# Sheet3.net
KiCad netlist of a schematic drawn in Altium Designer
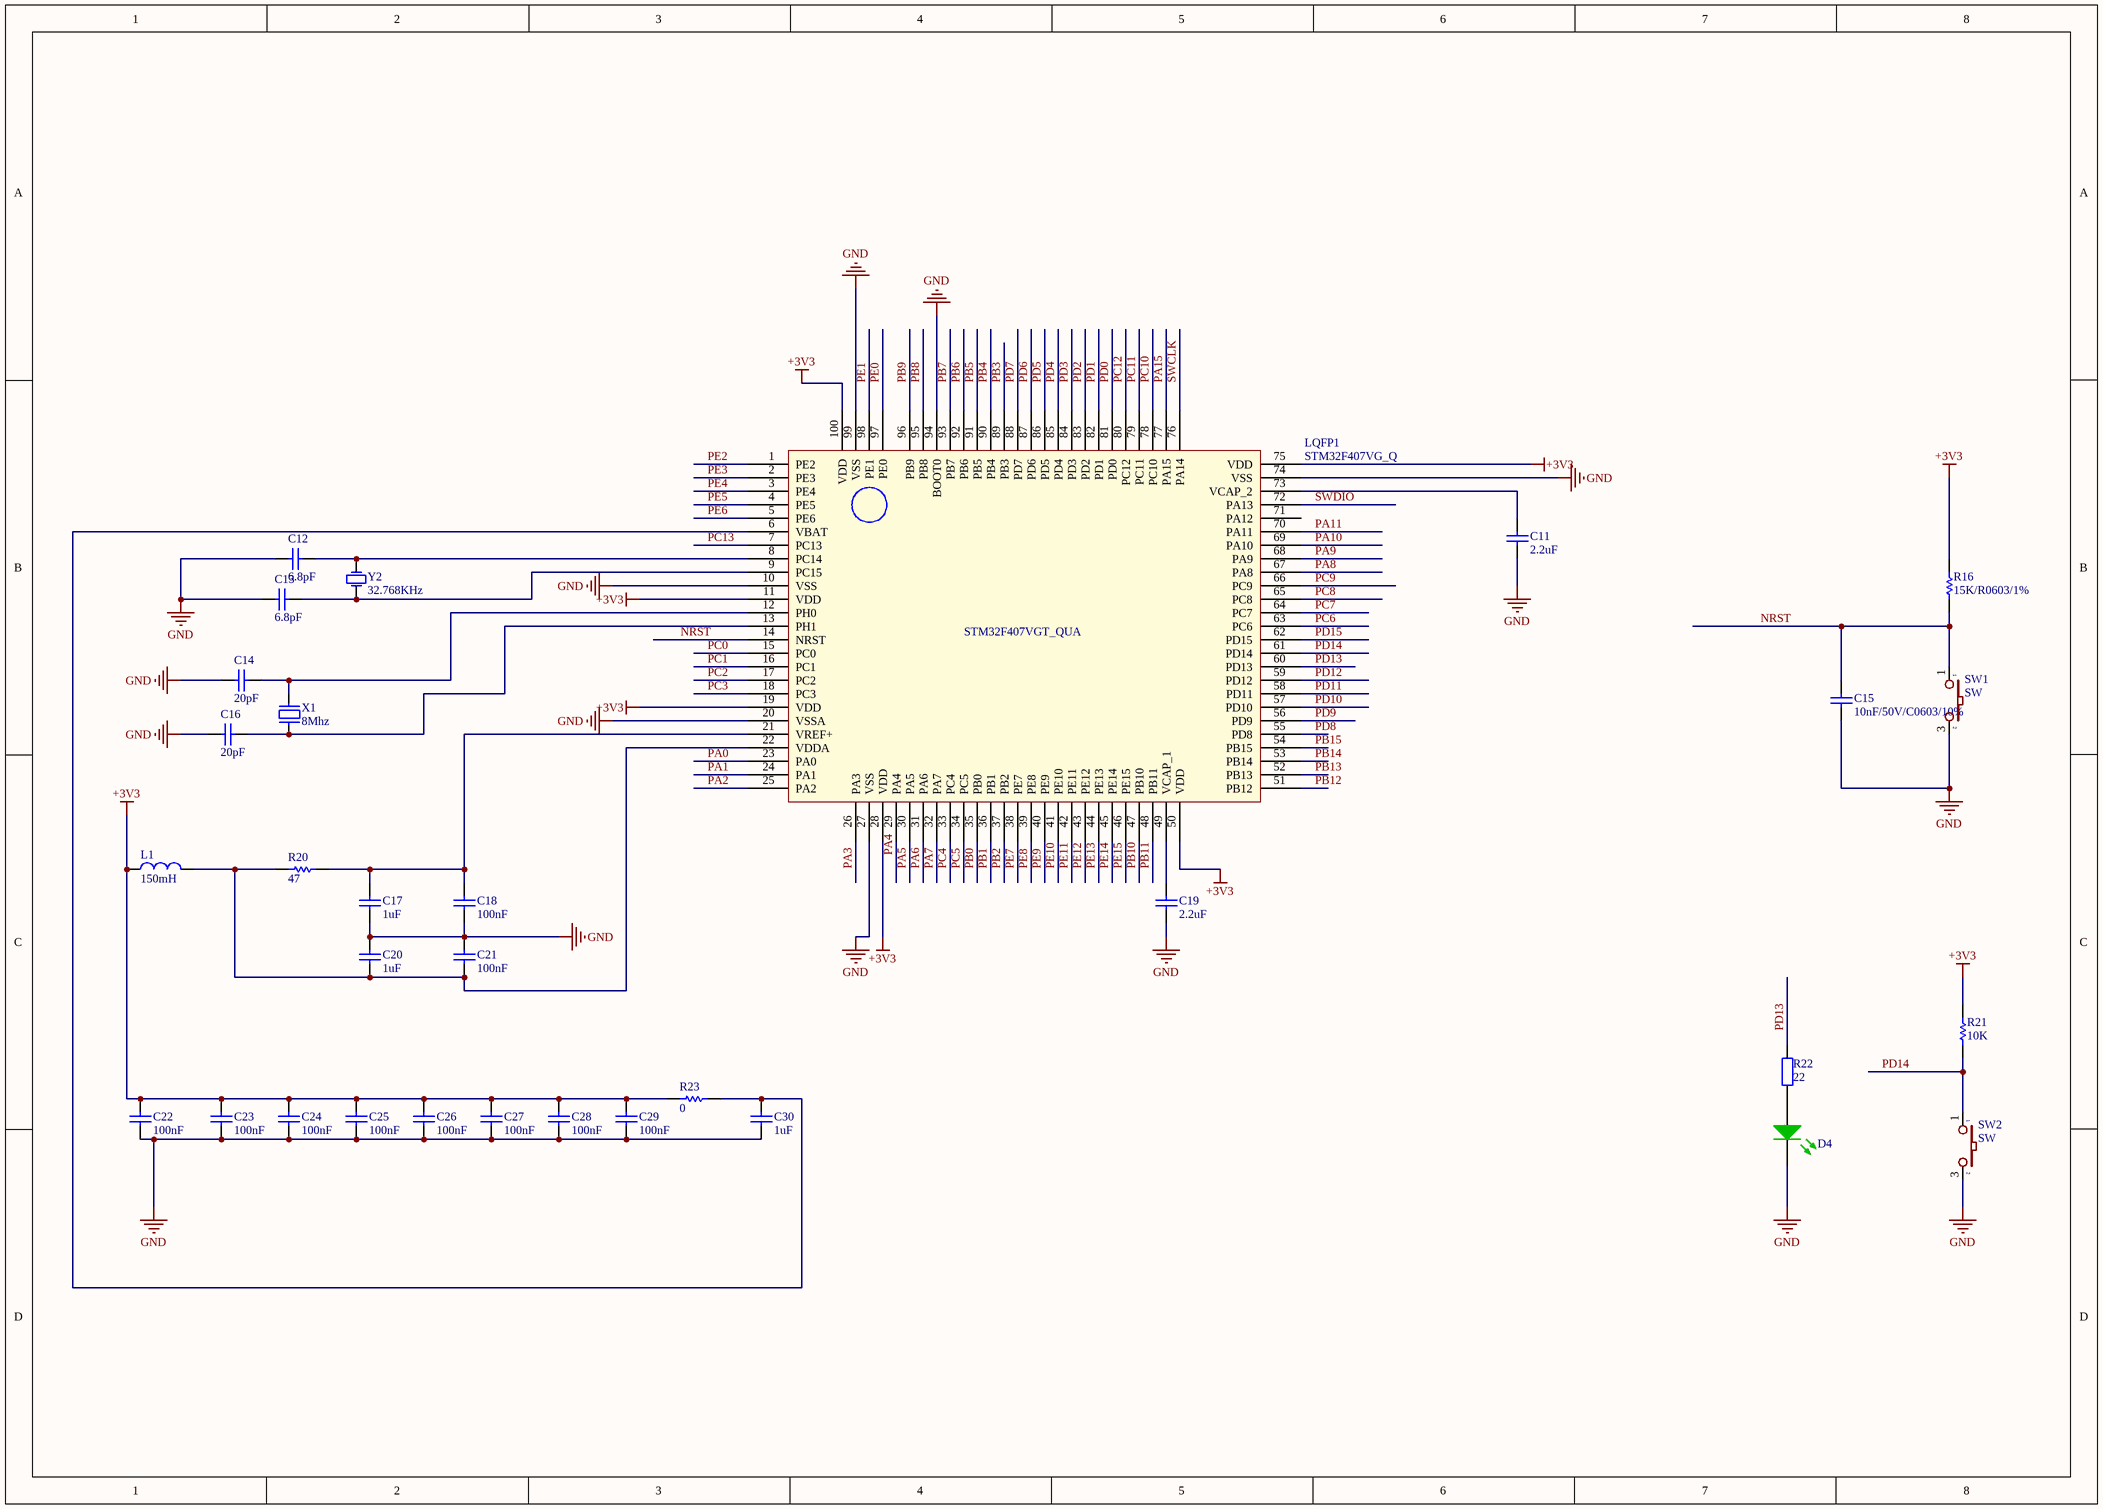
[diagram p0: Sheet3.SchDoc]

(export (version "E")
  (design (tool "Eeschema 10.0.6"))
  (components
    (comp (ref "C11")
      (value "2.2uF")
      (footprint "Cap Ceramic 0805 SMD")
      (description "CAP CER 22PF 50V NP0 0603")
      (fields
        (field (name "MANUFACTURER") "Kemet")
        (field (name "MANUFACTURER PART NUMBER") "C0603C220K5GACTU")
      )
      (libsource (lib "lpson") (part "22pF/50V/C0603/10%"))
    )
    (comp (ref "C12")
      (value "6.8pF")
      (footprint "Cap Ceramic 0805 SMD")
      (description "CAP CER 22PF 50V NP0 0603")
      (fields
        (field (name "MANUFACTURER") "Kemet")
        (field (name "MANUFACTURER PART NUMBER") "C0603C220K5GACTU")
      )
      (libsource (lib "lpson") (part "22pF/50V/C0603/10%"))
    )
    (comp (ref "C13")
      (value "6.8pF")
      (footprint "Cap Ceramic 0805 SMD")
      (description "CAP CER 22PF 50V NP0 0603")
      (fields
        (field (name "MANUFACTURER") "Kemet")
        (field (name "MANUFACTURER PART NUMBER") "C0603C220K5GACTU")
      )
      (libsource (lib "lpson") (part "22pF/50V/C0603/10%"))
    )
    (comp (ref "C14")
      (value "20pF")
      (footprint "Cap Ceramic 0805 SMD")
      (description "CAP CER 22PF 50V NP0 0603")
      (fields
        (field (name "MANUFACTURER") "Kemet")
        (field (name "MANUFACTURER PART NUMBER") "C0603C220K5GACTU")
      )
      (libsource (lib "lpson") (part "22pF/50V/C0603/10%"))
    )
    (comp (ref "C15")
      (value "10nF/50V/C0603/10%")
      (footprint "Cap Ceramic 0805 SMD")
      (description "CAP CER 10000PF 50V X7R 0603")
      (fields
        (field (name "MANUFACTURER") "Murata Electronics North America")
        (field (name "MANUFACTURER PART NUMBER") "GRM188R71H103KA01D")
      )
      (libsource (lib "lpson") (part "10nF/50V/C0603/10%_1"))
    )
    (comp (ref "C16")
      (value "20pF")
      (footprint "Cap Ceramic 0805 SMD")
      (description "CAP CER 22PF 50V NP0 0603")
      (fields
        (field (name "MANUFACTURER") "Kemet")
        (field (name "MANUFACTURER PART NUMBER") "C0603C220K5GACTU")
      )
      (libsource (lib "lpson") (part "22pF/50V/C0603/10%"))
    )
    (comp (ref "C17")
      (value "1uF")
      (footprint "Cap Ceramic 0805 SMD")
      (description "CAP CER 22PF 50V NP0 0603")
      (fields
        (field (name "MANUFACTURER") "Kemet")
        (field (name "MANUFACTURER PART NUMBER") "C0603C220K5GACTU")
      )
      (libsource (lib "lpson") (part "22pF/50V/C0603/10%"))
    )
    (comp (ref "C18")
      (value "100nF")
      (footprint "Cap Ceramic 0805 SMD")
      (description "CAP CER 22PF 50V NP0 0603")
      (fields
        (field (name "MANUFACTURER") "Kemet")
        (field (name "MANUFACTURER PART NUMBER") "C0603C220K5GACTU")
      )
      (libsource (lib "lpson") (part "22pF/50V/C0603/10%"))
    )
    (comp (ref "C19")
      (value "2.2uF")
      (footprint "Cap Ceramic 0805 SMD")
      (description "CAP CER 22PF 50V NP0 0603")
      (fields
        (field (name "MANUFACTURER") "Kemet")
        (field (name "MANUFACTURER PART NUMBER") "C0603C220K5GACTU")
      )
      (libsource (lib "lpson") (part "22pF/50V/C0603/10%"))
    )
    (comp (ref "C20")
      (value "1uF")
      (footprint "Cap Ceramic 0805 SMD")
      (description "CAP CER 22PF 50V NP0 0603")
      (fields
        (field (name "MANUFACTURER") "Kemet")
        (field (name "MANUFACTURER PART NUMBER") "C0603C220K5GACTU")
      )
      (libsource (lib "lpson") (part "22pF/50V/C0603/10%"))
    )
    (comp (ref "C21")
      (value "100nF")
      (footprint "Cap Ceramic 0805 SMD")
      (description "CAP CER 22PF 50V NP0 0603")
      (fields
        (field (name "MANUFACTURER") "Kemet")
        (field (name "MANUFACTURER PART NUMBER") "C0603C220K5GACTU")
      )
      (libsource (lib "lpson") (part "22pF/50V/C0603/10%"))
    )
    (comp (ref "C22")
      (value "100nF")
      (footprint "Cap Ceramic 0805 SMD")
      (description "CAP CER 22PF 50V NP0 0603")
      (fields
        (field (name "MANUFACTURER") "Kemet")
        (field (name "MANUFACTURER PART NUMBER") "C0603C220K5GACTU")
      )
      (libsource (lib "lpson") (part "22pF/50V/C0603/10%"))
    )
    (comp (ref "C23")
      (value "100nF")
      (footprint "Cap Ceramic 0805 SMD")
      (description "CAP CER 22PF 50V NP0 0603")
      (fields
        (field (name "MANUFACTURER") "Kemet")
        (field (name "MANUFACTURER PART NUMBER") "C0603C220K5GACTU")
      )
      (libsource (lib "lpson") (part "22pF/50V/C0603/10%"))
    )
    (comp (ref "C24")
      (value "100nF")
      (footprint "Cap Ceramic 0805 SMD")
      (description "CAP CER 22PF 50V NP0 0603")
      (fields
        (field (name "MANUFACTURER") "Kemet")
        (field (name "MANUFACTURER PART NUMBER") "C0603C220K5GACTU")
      )
      (libsource (lib "lpson") (part "22pF/50V/C0603/10%"))
    )
    (comp (ref "C25")
      (value "100nF")
      (footprint "Cap Ceramic 0805 SMD")
      (description "CAP CER 22PF 50V NP0 0603")
      (fields
        (field (name "MANUFACTURER") "Kemet")
        (field (name "MANUFACTURER PART NUMBER") "C0603C220K5GACTU")
      )
      (libsource (lib "lpson") (part "22pF/50V/C0603/10%"))
    )
    (comp (ref "C26")
      (value "100nF")
      (footprint "Cap Ceramic 0805 SMD")
      (description "CAP CER 22PF 50V NP0 0603")
      (fields
        (field (name "MANUFACTURER") "Kemet")
        (field (name "MANUFACTURER PART NUMBER") "C0603C220K5GACTU")
      )
      (libsource (lib "lpson") (part "22pF/50V/C0603/10%"))
    )
    (comp (ref "C27")
      (value "100nF")
      (footprint "Cap Ceramic 0805 SMD")
      (description "CAP CER 22PF 50V NP0 0603")
      (fields
        (field (name "MANUFACTURER") "Kemet")
        (field (name "MANUFACTURER PART NUMBER") "C0603C220K5GACTU")
      )
      (libsource (lib "lpson") (part "22pF/50V/C0603/10%"))
    )
    (comp (ref "C28")
      (value "100nF")
      (footprint "Cap Ceramic 0805 SMD")
      (description "CAP CER 22PF 50V NP0 0603")
      (fields
        (field (name "MANUFACTURER") "Kemet")
        (field (name "MANUFACTURER PART NUMBER") "C0603C220K5GACTU")
      )
      (libsource (lib "lpson") (part "22pF/50V/C0603/10%"))
    )
    (comp (ref "C29")
      (value "100nF")
      (footprint "Cap Ceramic 0805 SMD")
      (description "CAP CER 22PF 50V NP0 0603")
      (fields
        (field (name "MANUFACTURER") "Kemet")
        (field (name "MANUFACTURER PART NUMBER") "C0603C220K5GACTU")
      )
      (libsource (lib "lpson") (part "22pF/50V/C0603/10%"))
    )
    (comp (ref "C30")
      (value "1uF")
      (footprint "Cap Ceramic 0805 SMD")
      (description "CAP CER 22PF 50V NP0 0603")
      (fields
        (field (name "MANUFACTURER") "Kemet")
        (field (name "MANUFACTURER PART NUMBER") "C0603C220K5GACTU")
      )
      (libsource (lib "lpson") (part "22pF/50V/C0603/10%"))
    )
    (comp (ref "D4")
      (value "GREEN 0603")
      (footprint "Led 0805G")
      (description "LED GREEN CLEAR 0603 SMD")
      (fields
        (field (name "MANUFACTURER") "Lite-On Inc.")
        (field (name "MANUFACTURER PART NUMBER") "LTST-C190KGKT")
      )
      (libsource (lib "STLINKv2DIYmơi") (part "LED GREEN 0603"))
    )
    (comp (ref "L1")
      (value "150mH")
      (footprint "Res 0805 SMD")
      (description "Inductor")
      (libsource (lib "lpson") (part "L1"))
    )
    (comp (ref "LQFP1")
      (value "STM32F407VG_Q")
      (footprint "LPON_IC:STM32F407VG")
      (libsource (lib "SchSTM32F407VGT") (part "STM32F407VG_Q"))
    )
    (comp (ref "R16")
      (value "15K/R0603/1%")
      (footprint "Res 0805 SMD")
      (description "RES SMD 15K OHM 1% 1/10W 0603")
      (fields
        (field (name "MANUFACTURER") "Yageo")
        (field (name "MANUFACTURER PART NUMBER") "RC0603FR-0715KL")
      )
      (libsource (lib "lpson") (part "15K/R0603/1%_1"))
    )
    (comp (ref "R20")
      (value "47")
      (footprint "Res 0805 SMD")
      (description "RES SMD 10K OHM 1% 1/10W 0603")
      (fields
        (field (name "MANUFACTURER") "Yageo")
        (field (name "MANUFACTURER PART NUMBER") "RC0603FR-0710KL")
      )
      (libsource (lib "lpson") (part "10K/R0603/1%"))
    )
    (comp (ref "R21")
      (value "10K")
      (footprint "Res 0805 SMD")
      (description "RES SMD 15K OHM 1% 1/10W 0603")
      (fields
        (field (name "MANUFACTURER") "Yageo")
        (field (name "MANUFACTURER PART NUMBER") "RC0603FR-0715KL")
      )
      (libsource (lib "lpson") (part "15K/R0603/1%_1"))
    )
    (comp (ref "R22")
      (value "22")
      (footprint "Res 0805 SMD")
      (description "Resistor")
      (fields (field (name "Comment") "Res2") (field (name "PUBLISHER") "Altium Limited"))
      (libsource (lib "STLINKv2DIYmơi") (part "Res2"))
    )
    (comp (ref "R23")
      (value "0")
      (footprint "Res 0805 SMD")
      (description "RES SMD 10K OHM 1% 1/10W 0603")
      (fields
        (field (name "MANUFACTURER") "Yageo")
        (field (name "MANUFACTURER PART NUMBER") "RC0603FR-0710KL")
      )
      (libsource (lib "lpson") (part "10K/R0603/1%"))
    )
    (comp (ref "SW1")
      (value "SW")
      (footprint "BUTTON 4 PIN")
      (description "Switch button 2 pin")
      (libsource (lib "lpson") (part "SW2"))
    )
    (comp (ref "SW2")
      (value "SW")
      (footprint "BUTTON 4 PIN")
      (description "Switch button 2 pin")
      (libsource (lib "lpson") (part "SW2"))
    )
    (comp (ref "X1")
      (value "8Mhz")
      (footprint "CRYSTAL")
      (description "Crystal 32,768kHz for timer real")
      (libsource (lib "lpson") (part "XT32k"))
    )
    (comp (ref "Y2")
      (value "32.768KHz")
      (footprint "CR_32768")
      (description "Crystal FC-135R - 32.768KHz")
      (fields (field (name "Comment") "FC-135R - 32.768KHz"))
      (libsource (lib "lpson") (part "FC-135R - 32.768KHz"))
    )
  )
  (nets
    (net (code "1") (name "+3V3") (class "Default")
      (node (ref "C22") (pin "2") (pinfunction "2_2") (pintype "passive"))
      (node (ref "C23") (pin "2") (pinfunction "2_2") (pintype "passive"))
      (node (ref "C24") (pin "2") (pinfunction "2_2") (pintype "passive"))
      (node (ref "C25") (pin "2") (pinfunction "2_2") (pintype "passive"))
      (node (ref "C26") (pin "2") (pinfunction "2_2") (pintype "passive"))
      (node (ref "C27") (pin "2") (pinfunction "2_2") (pintype "passive"))
      (node (ref "C28") (pin "2") (pinfunction "2_2") (pintype "passive"))
      (node (ref "C29") (pin "2") (pinfunction "2_2") (pintype "passive"))
      (node (ref "L1") (pin "1") (pinfunction "1_1") (pintype "passive"))
      (node (ref "LQFP1") (pin "100") (pinfunction "VDD_100") (pintype "passive"))
      (node (ref "LQFP1") (pin "11") (pinfunction "VDD_11") (pintype "passive"))
      (node (ref "LQFP1") (pin "19") (pinfunction "VDD_19") (pintype "passive"))
      (node (ref "LQFP1") (pin "28") (pinfunction "VDD_28") (pintype "passive"))
      (node (ref "LQFP1") (pin "50") (pinfunction "VDD_50") (pintype "passive"))
      (node (ref "LQFP1") (pin "75") (pinfunction "VDD_75") (pintype "passive"))
      (node (ref "R16") (pin "2") (pinfunction "2_2") (pintype "passive"))
      (node (ref "R21") (pin "2") (pinfunction "2_2") (pintype "passive"))
      (node (ref "R23") (pin "2") (pinfunction "2_2") (pintype "passive"))
    )
    (net (code "2") (name "/NRST") (class "Default")
      (node (ref "C15") (pin "2") (pinfunction "2_2") (pintype "passive"))
      (node (ref "LQFP1") (pin "14") (pinfunction "NRST_14") (pintype "passive"))
      (node (ref "R16") (pin "1") (pinfunction "1_1") (pintype "passive"))
      (node (ref "SW1") (pin "1") (pinfunction "1_1") (pintype "passive"))
    )
    (net (code "3") (name "/PA0") (class "Default")
      (node (ref "LQFP1") (pin "23") (pinfunction "PA0_23") (pintype "passive"))
    )
    (net (code "4") (name "/PA1") (class "Default")
      (node (ref "LQFP1") (pin "24") (pinfunction "PA1_24") (pintype "passive"))
    )
    (net (code "5") (name "/PA2") (class "Default")
      (node (ref "LQFP1") (pin "25") (pinfunction "PA2_25") (pintype "passive"))
    )
    (net (code "6") (name "/PA3") (class "Default")
      (node (ref "LQFP1") (pin "26") (pinfunction "PA3_26") (pintype "passive"))
    )
    (net (code "7") (name "/PA4") (class "Default")
      (node (ref "LQFP1") (pin "29") (pinfunction "PA4_29") (pintype "passive"))
    )
    (net (code "8") (name "/PA5") (class "Default")
      (node (ref "LQFP1") (pin "30") (pinfunction "PA5_30") (pintype "passive"))
    )
    (net (code "9") (name "/PA6") (class "Default")
      (node (ref "LQFP1") (pin "31") (pinfunction "PA6_31") (pintype "passive"))
    )
    (net (code "10") (name "/PA7") (class "Default")
      (node (ref "LQFP1") (pin "32") (pinfunction "PA7_32") (pintype "passive"))
    )
    (net (code "11") (name "/PA8") (class "Default")
      (node (ref "LQFP1") (pin "67") (pinfunction "PA8_67") (pintype "passive"))
    )
    (net (code "12") (name "/PA9") (class "Default")
      (node (ref "LQFP1") (pin "68") (pinfunction "PA9_68") (pintype "passive"))
    )
    (net (code "13") (name "/PA10") (class "Default")
      (node (ref "LQFP1") (pin "69") (pinfunction "PA10_69") (pintype "passive"))
    )
    (net (code "14") (name "/PA11") (class "Default")
      (node (ref "LQFP1") (pin "70") (pinfunction "PA11_70") (pintype "passive"))
    )
    (net (code "15") (name "/PA15") (class "Default")
      (node (ref "LQFP1") (pin "77") (pinfunction "PA15_77") (pintype "passive"))
    )
    (net (code "16") (name "/PB0") (class "Default")
      (node (ref "LQFP1") (pin "35") (pinfunction "PB0_35") (pintype "passive"))
    )
    (net (code "17") (name "/PB1") (class "Default")
      (node (ref "LQFP1") (pin "36") (pinfunction "PB1_36") (pintype "passive"))
    )
    (net (code "18") (name "/PB2") (class "Default")
      (node (ref "LQFP1") (pin "37") (pinfunction "PB2_37") (pintype "passive"))
    )
    (net (code "19") (name "/PB3") (class "Default")
      (node (ref "LQFP1") (pin "89") (pinfunction "PB3_89") (pintype "passive"))
    )
    (net (code "20") (name "/PB4") (class "Default")
      (node (ref "LQFP1") (pin "90") (pinfunction "PB4_90") (pintype "passive"))
    )
    (net (code "21") (name "/PB5") (class "Default")
      (node (ref "LQFP1") (pin "91") (pinfunction "PB5_91") (pintype "passive"))
    )
    (net (code "22") (name "/PB6") (class "Default")
      (node (ref "LQFP1") (pin "92") (pinfunction "PB6_92") (pintype "passive"))
    )
    (net (code "23") (name "/PB7") (class "Default")
      (node (ref "LQFP1") (pin "93") (pinfunction "PB7_93") (pintype "passive"))
    )
    (net (code "24") (name "/PB8") (class "Default")
      (node (ref "LQFP1") (pin "95") (pinfunction "PB8_95") (pintype "passive"))
    )
    (net (code "25") (name "/PB9") (class "Default")
      (node (ref "LQFP1") (pin "96") (pinfunction "PB9_96") (pintype "passive"))
    )
    (net (code "26") (name "/PB10") (class "Default")
      (node (ref "LQFP1") (pin "47") (pinfunction "PB10_47") (pintype "passive"))
    )
    (net (code "27") (name "/PB11") (class "Default")
      (node (ref "LQFP1") (pin "48") (pinfunction "PB11_48") (pintype "passive"))
    )
    (net (code "28") (name "/PB12") (class "Default")
      (node (ref "LQFP1") (pin "51") (pinfunction "PB12_51") (pintype "passive"))
    )
    (net (code "29") (name "/PB13") (class "Default")
      (node (ref "LQFP1") (pin "52") (pinfunction "PB13_52") (pintype "passive"))
    )
    (net (code "30") (name "/PB14") (class "Default")
      (node (ref "LQFP1") (pin "53") (pinfunction "PB14_53") (pintype "passive"))
    )
    (net (code "31") (name "/PB15") (class "Default")
      (node (ref "LQFP1") (pin "54") (pinfunction "PB15_54") (pintype "passive"))
    )
    (net (code "32") (name "/PC0") (class "Default")
      (node (ref "LQFP1") (pin "15") (pinfunction "PC0_15") (pintype "passive"))
    )
    (net (code "33") (name "/PC1") (class "Default")
      (node (ref "LQFP1") (pin "16") (pinfunction "PC1_16") (pintype "passive"))
    )
    (net (code "34") (name "/PC2") (class "Default")
      (node (ref "LQFP1") (pin "17") (pinfunction "PC2_17") (pintype "passive"))
    )
    (net (code "35") (name "/PC3") (class "Default")
      (node (ref "LQFP1") (pin "18") (pinfunction "PC3_18") (pintype "passive"))
    )
    (net (code "36") (name "/PC4") (class "Default")
      (node (ref "LQFP1") (pin "33") (pinfunction "PC4_33") (pintype "passive"))
    )
    (net (code "37") (name "/PC5") (class "Default")
      (node (ref "LQFP1") (pin "34") (pinfunction "PC5_34") (pintype "passive"))
    )
    (net (code "38") (name "/PC6") (class "Default")
      (node (ref "LQFP1") (pin "63") (pinfunction "PC6_63") (pintype "passive"))
    )
    (net (code "39") (name "/PC7") (class "Default")
      (node (ref "LQFP1") (pin "64") (pinfunction "PC7_64") (pintype "passive"))
    )
    (net (code "40") (name "/PC8") (class "Default")
      (node (ref "LQFP1") (pin "65") (pinfunction "PC8_65") (pintype "passive"))
    )
    (net (code "41") (name "/PC9") (class "Default")
      (node (ref "LQFP1") (pin "66") (pinfunction "PC9_66") (pintype "passive"))
    )
    (net (code "42") (name "/PC10") (class "Default")
      (node (ref "LQFP1") (pin "78") (pinfunction "PC10_78") (pintype "passive"))
    )
    (net (code "43") (name "/PC11") (class "Default")
      (node (ref "LQFP1") (pin "79") (pinfunction "PC11_79") (pintype "passive"))
    )
    (net (code "44") (name "/PC12") (class "Default")
      (node (ref "LQFP1") (pin "80") (pinfunction "PC12_80") (pintype "passive"))
    )
    (net (code "45") (name "/PC13") (class "Default")
      (node (ref "LQFP1") (pin "7") (pinfunction "PC13_7") (pintype "passive"))
    )
    (net (code "46") (name "/PD0") (class "Default")
      (node (ref "LQFP1") (pin "81") (pinfunction "PD0_81") (pintype "passive"))
    )
    (net (code "47") (name "/PD1") (class "Default")
      (node (ref "LQFP1") (pin "82") (pinfunction "PD1_82") (pintype "passive"))
    )
    (net (code "48") (name "/PD2") (class "Default")
      (node (ref "LQFP1") (pin "83") (pinfunction "PD2_83") (pintype "passive"))
    )
    (net (code "49") (name "/PD3") (class "Default")
      (node (ref "LQFP1") (pin "84") (pinfunction "PD3_84") (pintype "passive"))
    )
    (net (code "50") (name "/PD4") (class "Default")
      (node (ref "LQFP1") (pin "85") (pinfunction "PD4_85") (pintype "passive"))
    )
    (net (code "51") (name "/PD5") (class "Default")
      (node (ref "LQFP1") (pin "86") (pinfunction "PD5_86") (pintype "passive"))
    )
    (net (code "52") (name "/PD6") (class "Default")
      (node (ref "LQFP1") (pin "87") (pinfunction "PD6_87") (pintype "passive"))
    )
    (net (code "53") (name "/PD7") (class "Default")
      (node (ref "LQFP1") (pin "88") (pinfunction "PD7_88") (pintype "passive"))
    )
    (net (code "54") (name "/PD8") (class "Default")
      (node (ref "LQFP1") (pin "55") (pinfunction "PD8_55") (pintype "passive"))
    )
    (net (code "55") (name "/PD9") (class "Default")
      (node (ref "LQFP1") (pin "56") (pinfunction "PD9_56") (pintype "passive"))
    )
    (net (code "56") (name "/PD10") (class "Default")
      (node (ref "LQFP1") (pin "57") (pinfunction "PD10_57") (pintype "passive"))
    )
    (net (code "57") (name "/PD11") (class "Default")
      (node (ref "LQFP1") (pin "58") (pinfunction "PD11_58") (pintype "passive"))
    )
    (net (code "58") (name "/PD12") (class "Default")
      (node (ref "LQFP1") (pin "59") (pinfunction "PD12_59") (pintype "passive"))
    )
    (net (code "59") (name "/PD13") (class "Default")
      (node (ref "LQFP1") (pin "60") (pinfunction "PD13_60") (pintype "passive"))
      (node (ref "R22") (pin "1") (pinfunction "1_1") (pintype "passive"))
    )
    (net (code "60") (name "/PD14") (class "Default")
      (node (ref "LQFP1") (pin "61") (pinfunction "PD14_61") (pintype "passive"))
      (node (ref "R21") (pin "1") (pinfunction "1_1") (pintype "passive"))
      (node (ref "SW2") (pin "1") (pinfunction "1_1") (pintype "passive"))
    )
    (net (code "61") (name "/PD15") (class "Default")
      (node (ref "LQFP1") (pin "62") (pinfunction "PD15_62") (pintype "passive"))
    )
    (net (code "62") (name "/PE0") (class "Default")
      (node (ref "LQFP1") (pin "97") (pinfunction "PE0_97") (pintype "passive"))
    )
    (net (code "63") (name "/PE1") (class "Default")
      (node (ref "LQFP1") (pin "98") (pinfunction "PE1_98") (pintype "passive"))
    )
    (net (code "64") (name "/PE2") (class "Default")
      (node (ref "LQFP1") (pin "1") (pinfunction "PE2_1") (pintype "passive"))
    )
    (net (code "65") (name "/PE3") (class "Default")
      (node (ref "LQFP1") (pin "2") (pinfunction "PE3_2") (pintype "passive"))
    )
    (net (code "66") (name "/PE4") (class "Default")
      (node (ref "LQFP1") (pin "3") (pinfunction "PE4_3") (pintype "passive"))
    )
    (net (code "67") (name "/PE5") (class "Default")
      (node (ref "LQFP1") (pin "4") (pinfunction "PE5_4") (pintype "passive"))
    )
    (net (code "68") (name "/PE6") (class "Default")
      (node (ref "LQFP1") (pin "5") (pinfunction "PE6_5") (pintype "passive"))
    )
    (net (code "69") (name "/PE7") (class "Default")
      (node (ref "LQFP1") (pin "38") (pinfunction "PE7_38") (pintype "passive"))
    )
    (net (code "70") (name "/PE8") (class "Default")
      (node (ref "LQFP1") (pin "39") (pinfunction "PE8_39") (pintype "passive"))
    )
    (net (code "71") (name "/PE9") (class "Default")
      (node (ref "LQFP1") (pin "40") (pinfunction "PE9_40") (pintype "passive"))
    )
    (net (code "72") (name "/PE10") (class "Default")
      (node (ref "LQFP1") (pin "41") (pinfunction "PE10_41") (pintype "passive"))
    )
    (net (code "73") (name "/PE11") (class "Default")
      (node (ref "LQFP1") (pin "42") (pinfunction "PE11_42") (pintype "passive"))
    )
    (net (code "74") (name "/PE12") (class "Default")
      (node (ref "LQFP1") (pin "43") (pinfunction "PE12_43") (pintype "passive"))
    )
    (net (code "75") (name "/PE13") (class "Default")
      (node (ref "LQFP1") (pin "44") (pinfunction "PE13_44") (pintype "passive"))
    )
    (net (code "76") (name "/PE14") (class "Default")
      (node (ref "LQFP1") (pin "45") (pinfunction "PE14_45") (pintype "passive"))
    )
    (net (code "77") (name "/PE15") (class "Default")
      (node (ref "LQFP1") (pin "46") (pinfunction "PE15_46") (pintype "passive"))
    )
    (net (code "78") (name "/SWCLK") (class "Default")
      (node (ref "LQFP1") (pin "76") (pinfunction "PA14_76") (pintype "passive"))
    )
    (net (code "79") (name "/SWDIO") (class "Default")
      (node (ref "LQFP1") (pin "72") (pinfunction "PA13_72") (pintype "passive"))
    )
    (net (code "80") (name "GND") (class "Default")
      (node (ref "C11") (pin "1") (pinfunction "1_1") (pintype "passive"))
      (node (ref "C12") (pin "2") (pinfunction "2_2") (pintype "passive"))
      (node (ref "C13") (pin "2") (pinfunction "2_2") (pintype "passive"))
      (node (ref "C14") (pin "2") (pinfunction "2_2") (pintype "passive"))
      (node (ref "C15") (pin "1") (pinfunction "1_1") (pintype "passive"))
      (node (ref "C16") (pin "2") (pinfunction "2_2") (pintype "passive"))
      (node (ref "C17") (pin "1") (pinfunction "1_1") (pintype "passive"))
      (node (ref "C18") (pin "1") (pinfunction "1_1") (pintype "passive"))
      (node (ref "C19") (pin "1") (pinfunction "1_1") (pintype "passive"))
      (node (ref "C20") (pin "2") (pinfunction "2_2") (pintype "passive"))
      (node (ref "C21") (pin "2") (pinfunction "2_2") (pintype "passive"))
      (node (ref "C22") (pin "1") (pinfunction "1_1") (pintype "passive"))
      (node (ref "C23") (pin "1") (pinfunction "1_1") (pintype "passive"))
      (node (ref "C24") (pin "1") (pinfunction "1_1") (pintype "passive"))
      (node (ref "C25") (pin "1") (pinfunction "1_1") (pintype "passive"))
      (node (ref "C26") (pin "1") (pinfunction "1_1") (pintype "passive"))
      (node (ref "C27") (pin "1") (pinfunction "1_1") (pintype "passive"))
      (node (ref "C28") (pin "1") (pinfunction "1_1") (pintype "passive"))
      (node (ref "C29") (pin "1") (pinfunction "1_1") (pintype "passive"))
      (node (ref "C30") (pin "1") (pinfunction "1_1") (pintype "passive"))
      (node (ref "D4") (pin "2") (pinfunction "K_2") (pintype "passive"))
      (node (ref "LQFP1") (pin "10") (pinfunction "VSS_10") (pintype "passive"))
      (node (ref "LQFP1") (pin "20") (pinfunction "VSSA_20") (pintype "passive"))
      (node (ref "LQFP1") (pin "27") (pinfunction "VSS_27") (pintype "passive"))
      (node (ref "LQFP1") (pin "74") (pinfunction "VSS_74") (pintype "passive"))
      (node (ref "LQFP1") (pin "94") (pinfunction "BOOT0_94") (pintype "passive"))
      (node (ref "LQFP1") (pin "99") (pinfunction "VSS_99") (pintype "passive"))
      (node (ref "SW1") (pin "3") (pinfunction "3_3") (pintype "passive"))
      (node (ref "SW2") (pin "3") (pinfunction "3_3") (pintype "passive"))
    )
    (net (code "81") (name "Net-(D4-A)") (class "Default")
      (node (ref "D4") (pin "1") (pinfunction "A_1") (pintype "passive"))
      (node (ref "R22") (pin "2") (pinfunction "2_2") (pintype "passive"))
    )
    (net (code "82") (name "Net-(LQFP1-PC14)") (class "Default")
      (node (ref "C12") (pin "1") (pinfunction "1_1") (pintype "passive"))
      (node (ref "LQFP1") (pin "8") (pinfunction "PC14_8") (pintype "passive"))
      (node (ref "Y2") (pin "2") (pinfunction "OSC2_2") (pintype "passive"))
    )
    (net (code "83") (name "Net-(LQFP1-PC15)") (class "Default")
      (node (ref "C13") (pin "1") (pinfunction "1_1") (pintype "passive"))
      (node (ref "LQFP1") (pin "9") (pinfunction "PC15_9") (pintype "passive"))
      (node (ref "Y2") (pin "1") (pinfunction "OSC1_1") (pintype "passive"))
    )
    (net (code "84") (name "Net-(LQFP1-PH0)") (class "Default")
      (node (ref "C14") (pin "1") (pinfunction "1_1") (pintype "passive"))
      (node (ref "LQFP1") (pin "12") (pinfunction "PH0_12") (pintype "passive"))
      (node (ref "X1") (pin "2") (pinfunction "2_2") (pintype "passive"))
    )
    (net (code "85") (name "Net-(LQFP1-PH1)") (class "Default")
      (node (ref "C16") (pin "1") (pinfunction "1_1") (pintype "passive"))
      (node (ref "LQFP1") (pin "13") (pinfunction "PH1_13") (pintype "passive"))
      (node (ref "X1") (pin "1") (pinfunction "1_1") (pintype "passive"))
    )
    (net (code "86") (name "Net-(LQFP1-VBAT)") (class "Default")
      (node (ref "C30") (pin "2") (pinfunction "2_2") (pintype "passive"))
      (node (ref "LQFP1") (pin "6") (pinfunction "VBAT_6") (pintype "passive"))
      (node (ref "R23") (pin "1") (pinfunction "1_1") (pintype "passive"))
    )
    (net (code "87") (name "Net-(LQFP1-VCAP_1)") (class "Default")
      (node (ref "C19") (pin "2") (pinfunction "2_2") (pintype "passive"))
      (node (ref "LQFP1") (pin "49") (pinfunction "VCAP_1_49") (pintype "passive"))
    )
    (net (code "88") (name "Net-(LQFP1-VCAP_2)") (class "Default")
      (node (ref "C11") (pin "2") (pinfunction "2_2") (pintype "passive"))
      (node (ref "LQFP1") (pin "73") (pinfunction "VCAP_2_73") (pintype "passive"))
    )
    (net (code "89") (name "Net-(LQFP1-VDDA)") (class "Default")
      (node (ref "C20") (pin "1") (pinfunction "1_1") (pintype "passive"))
      (node (ref "C21") (pin "1") (pinfunction "1_1") (pintype "passive"))
      (node (ref "L1") (pin "2") (pinfunction "2_2") (pintype "passive"))
      (node (ref "LQFP1") (pin "22") (pinfunction "VDDA_22") (pintype "passive"))
      (node (ref "R20") (pin "2") (pinfunction "2_2") (pintype "passive"))
    )
    (net (code "90") (name "Net-(LQFP1-VREF+)") (class "Default")
      (node (ref "C17") (pin "2") (pinfunction "2_2") (pintype "passive"))
      (node (ref "C18") (pin "2") (pinfunction "2_2") (pintype "passive"))
      (node (ref "LQFP1") (pin "21") (pinfunction "VREF+_21") (pintype "passive"))
      (node (ref "R20") (pin "1") (pinfunction "1_1") (pintype "passive"))
    )
    (net (code "91") (name "unconnected-(LQFP1-PA12-Pad71)") (class "Default")
      (node (ref "LQFP1") (pin "71") (pinfunction "PA12_71") (pintype "passive"))
    )
  )
)
